# Cricket.net
KiCad netlist of a schematic drawn in EAGLE
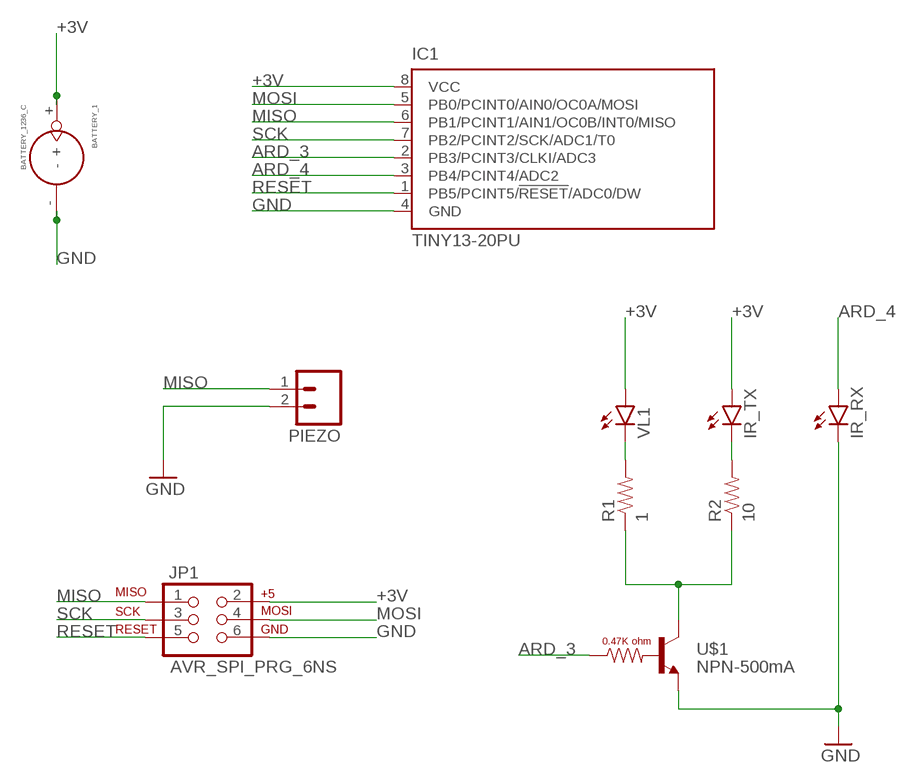
[diagram p0: schematic, sheet 1]

(export (version "E")
  (design (tool "Eeschema 10.0.6"))
  (components
    (comp (ref "BATTERY_1")
      (value "BATTERY_1236_C")
      (footprint "eagle-import:BATTERY_1236_C")
      (libsource (lib "eagle-import") (part "BATTERY_1236_C"))
    )
    (comp (ref "IC1")
      (value "TINY13-20PU")
      (footprint "eagle-import:DIL08")
      (fields (field (name "MPN") "ATTINY13-20PU"))
      (libsource (lib "eagle-import") (part "TINY13PU-20"))
    )
    (comp (ref "IR_RX")
      (value "LED5MM")
      (footprint "eagle-import:LED5MM")
      (fields (field (name "MFG") "OSRAM Opto") (field (name "MPN") "SFH206K"))
      (libsource (lib "eagle-import") (part "LED5MM"))
    )
    (comp (ref "IR_TX")
      (value "LED5MM")
      (footprint "eagle-import:LED5MM")
      (fields (field (name "MFG") "TT Electronics / Optek Technology") (field (name "MPN") "OP293B"))
      (libsource (lib "eagle-import") (part "LED5MM"))
    )
    (comp (ref "JP1")
      (value "AVR_SPI_PRG_6NS")
      (footprint "eagle-import:2X3-NS")
      (libsource (lib "eagle-import") (part "AVR_SPI_PRG_6NS"))
    )
    (comp (ref "PIEZO")
      (value "M02PTH")
      (footprint "eagle-import:1X02")
      (libsource (lib "eagle-import") (part "M02PTH"))
    )
    (comp (ref "R1")
      (value "1")
      (footprint "eagle-import:1206")
      (libsource (lib "eagle-import") (part "RESISTOR1206"))
    )
    (comp (ref "R2")
      (value "10")
      (footprint "eagle-import:1206")
      (libsource (lib "eagle-import") (part "RESISTOR1206"))
    )
    (comp (ref "U$1")
      (value "NPN-500mA")
      (footprint "eagle-import:SOT23-3")
      (libsource (lib "eagle-import") (part "TRANSISTOR-NPN-DDTD142TC"))
    )
    (comp (ref "VL1")
      (value "LED5MM")
      (footprint "eagle-import:LED5MM")
      (fields (field (name "MFG") "TT Electronics / Optek Technology") (field (name "MPN") "OP293B"))
      (libsource (lib "eagle-import") (part "LED5MM"))
    )
  )
  (nets
    (net (code "1") (name "/+3V") (class "Default")
      (node (ref "BATTERY_1") (pin "+") (pinfunction "+_+") (pintype "bidirectional"))
      (node (ref "IC1") (pin "8") (pinfunction "VCC_8") (pintype "power_in"))
      (node (ref "IR_TX") (pin "A") (pinfunction "A_A") (pintype "passive"))
      (node (ref "JP1") (pin "2") (pinfunction "2_2") (pintype "passive"))
      (node (ref "VL1") (pin "A") (pinfunction "A_A") (pintype "passive"))
    )
    (net (code "2") (name "/ARD_3") (class "Default")
      (node (ref "IC1") (pin "2") (pinfunction "PB3/PCINT3/CLKI/ADC3_2") (pintype "bidirectional"))
      (node (ref "U$1") (pin "1") (pinfunction "B_1") (pintype "passive"))
    )
    (net (code "3") (name "/ARD_4") (class "Default")
      (node (ref "IC1") (pin "3") (pinfunction "PB4/PCINT4/ADC2_3") (pintype "bidirectional"))
      (node (ref "IR_RX") (pin "A") (pinfunction "A_A") (pintype "passive"))
    )
    (net (code "4") (name "/MISO") (class "Default")
      (node (ref "IC1") (pin "6") (pinfunction "PB1/PCINT1/AIN1/OC0B/INT0/MISO_6") (pintype "bidirectional"))
      (node (ref "JP1") (pin "1") (pinfunction "1_1") (pintype "passive"))
      (node (ref "PIEZO") (pin "1") (pinfunction "1_1") (pintype "passive"))
    )
    (net (code "5") (name "/MOSI") (class "Default")
      (node (ref "IC1") (pin "5") (pinfunction "PB0/PCINT0/AIN0/OC0A/MOSI_5") (pintype "bidirectional"))
      (node (ref "JP1") (pin "4") (pinfunction "4_4") (pintype "passive"))
    )
    (net (code "6") (name "/RESET") (class "Default")
      (node (ref "IC1") (pin "1") (pinfunction "PB5/PCINT5/~{RESET}/ADC0/DW_1") (pintype "bidirectional"))
      (node (ref "JP1") (pin "5") (pinfunction "5_5") (pintype "passive"))
    )
    (net (code "7") (name "/SCK") (class "Default")
      (node (ref "IC1") (pin "7") (pinfunction "PB2/PCINT2/SCK/ADC1/T0_7") (pintype "bidirectional"))
      (node (ref "JP1") (pin "3") (pinfunction "3_3") (pintype "passive"))
    )
    (net (code "8") (name "GND") (class "Default")
      (node (ref "BATTERY_1") (pin "-") (pinfunction "-_-") (pintype "bidirectional"))
      (node (ref "IC1") (pin "4") (pinfunction "GND_4") (pintype "power_in"))
      (node (ref "IR_RX") (pin "K") (pinfunction "C_K") (pintype "passive"))
      (node (ref "JP1") (pin "6") (pinfunction "6_6") (pintype "passive"))
      (node (ref "PIEZO") (pin "2") (pinfunction "2_2") (pintype "passive"))
      (node (ref "U$1") (pin "2") (pinfunction "E_2") (pintype "passive"))
    )
    (net (code "9") (name "Net-(IR_TX-C)") (class "Default")
      (node (ref "IR_TX") (pin "K") (pinfunction "C_K") (pintype "passive"))
      (node (ref "R2") (pin "2") (pinfunction "2_2") (pintype "passive"))
    )
    (net (code "10") (name "Net-(U$1-C)") (class "Default")
      (node (ref "R1") (pin "1") (pinfunction "1_1") (pintype "passive"))
      (node (ref "R2") (pin "1") (pinfunction "1_1") (pintype "passive"))
      (node (ref "U$1") (pin "3") (pinfunction "C_3") (pintype "passive"))
    )
    (net (code "11") (name "Net-(VL1-C)") (class "Default")
      (node (ref "R1") (pin "2") (pinfunction "2_2") (pintype "passive"))
      (node (ref "VL1") (pin "K") (pinfunction "C_K") (pintype "passive"))
    )
  )
)
